# iCEBlaster.net
KiCad netlist of a schematic drawn in EAGLE
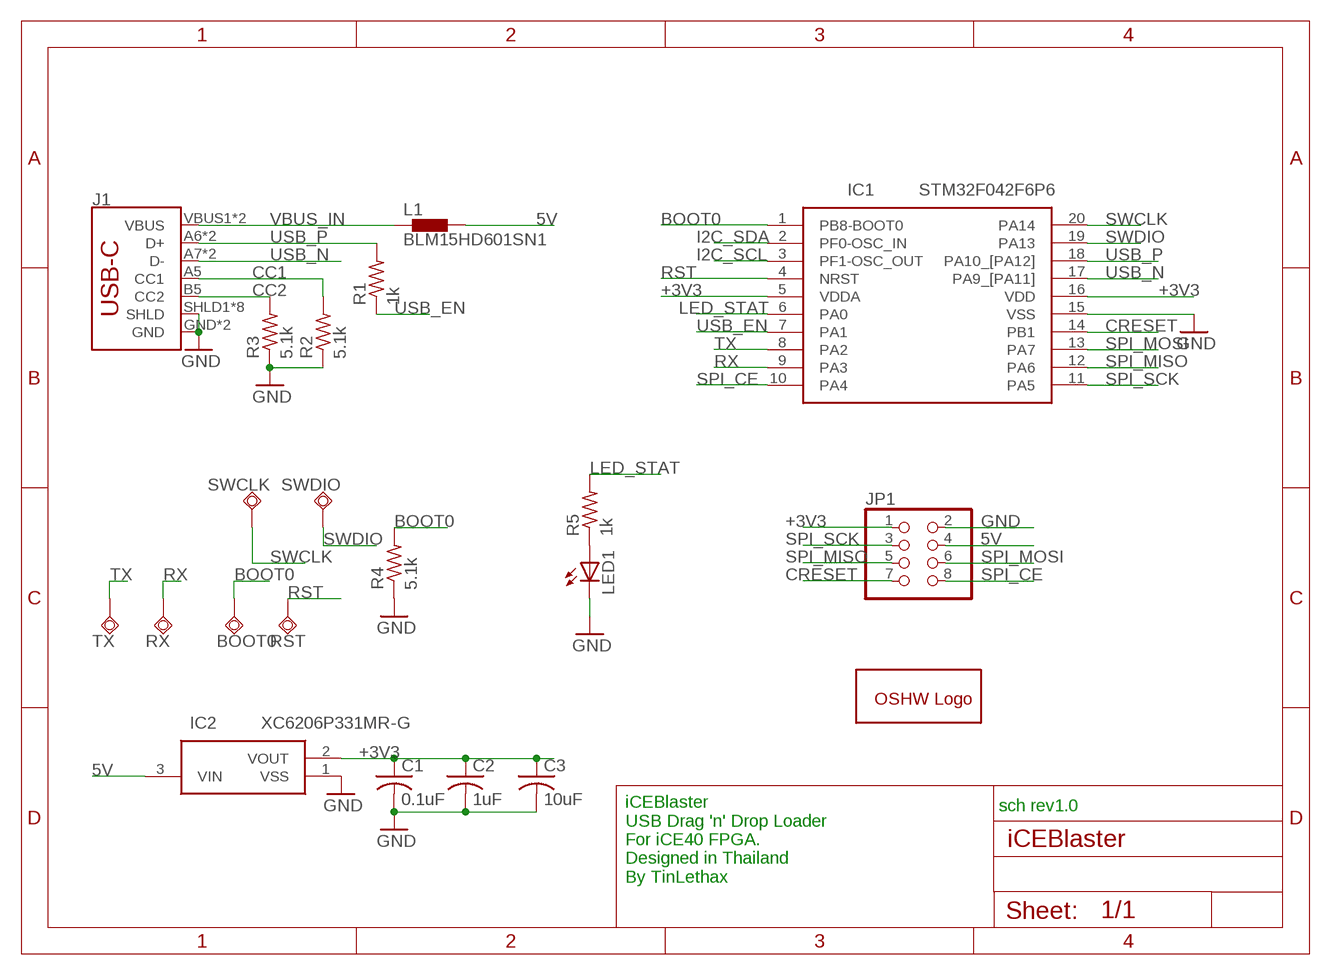
[diagram p0: schematic, sheet 1]

(export (version "E")
  (design (tool "Eeschema 10.0.6"))
  (components
    (comp (ref "BOOT0")
      (value "TPSQTP15SQ")
      (footprint "eagle-import:TP15SQ")
      (libsource (lib "eagle-import") (part "TPSQTP15SQ"))
    )
    (comp (ref "C1")
      (value "0.1uF")
      (footprint "eagle-import:C0603")
      (libsource (lib "eagle-import") (part "C-USC0603"))
    )
    (comp (ref "C2")
      (value "1uF")
      (footprint "eagle-import:C0603")
      (libsource (lib "eagle-import") (part "C-USC0603"))
    )
    (comp (ref "C3")
      (value "10uF")
      (footprint "eagle-import:C0603")
      (libsource (lib "eagle-import") (part "C-USC0603"))
    )
    (comp (ref "GOLD_ORB_SM1")
      (value "OSHWLOGOLOGO5MM")
      (footprint "eagle-import:OSHW_5MM")
      (libsource (lib "eagle-import") (part "OSHWLOGOLOGO5MM"))
    )
    (comp (ref "IC1")
      (value "STM32F042F6P6")
      (footprint "eagle-import:SOP65P640X120-20N")
      (fields (field (name "MOUSER_PART_NUMBER") "511-STM32F042F6P6"))
      (libsource (lib "eagle-import") (part "STM32F042F6P6"))
    )
    (comp (ref "IC2")
      (value "XC6206P331MR-G")
      (footprint "eagle-import:SOT95P280X130-3N")
      (fields (field (name "MOUSER_PART_NUMBER") "865-XC6206P331MR-G"))
      (libsource (lib "eagle-import") (part "XC6206P331MR-G"))
    )
    (comp (ref "J1")
      (value "SPARKFUN-CONNECTORS_USB_C16PIN")
      (footprint "eagle-import:SPARKFUN-CONNECTORS_USB-C-16P")
      (libsource (lib "eagle-import") (part "SPARKFUN-CONNECTORS_USB_C16PIN"))
    )
    (comp (ref "JP1")
      (value "PINHD-2X4/90")
      (footprint "eagle-import:2X04_90")
      (libsource (lib "eagle-import") (part "PINHD-2X4/90"))
    )
    (comp (ref "L1")
      (value "BLM15HD601SN1")
      (footprint "eagle-import:0402")
      (libsource (lib "eagle-import") (part "BLM15HD601SN1"))
    )
    (comp (ref "LED1")
      (value "LEDCHIP-LED0603")
      (footprint "eagle-import:CHIP-LED0603")
      (libsource (lib "eagle-import") (part "LEDCHIP-LED0603"))
    )
    (comp (ref "R1")
      (value "1k")
      (footprint "eagle-import:R0603")
      (libsource (lib "eagle-import") (part "R-US_R0603"))
    )
    (comp (ref "R2")
      (value "5.1k")
      (footprint "eagle-import:R0603")
      (libsource (lib "eagle-import") (part "R-US_R0603"))
    )
    (comp (ref "R3")
      (value "5.1k")
      (footprint "eagle-import:R0603")
      (libsource (lib "eagle-import") (part "R-US_R0603"))
    )
    (comp (ref "R4")
      (value "5.1k")
      (footprint "eagle-import:R0603")
      (libsource (lib "eagle-import") (part "R-US_R0603"))
    )
    (comp (ref "R5")
      (value "1k")
      (footprint "eagle-import:R0603")
      (libsource (lib "eagle-import") (part "R-US_R0603"))
    )
    (comp (ref "RST")
      (value "TPSQTP15SQ")
      (footprint "eagle-import:TP15SQ")
      (libsource (lib "eagle-import") (part "TPSQTP15SQ"))
    )
    (comp (ref "RX")
      (value "TPSQTP15SQ")
      (footprint "eagle-import:TP15SQ")
      (libsource (lib "eagle-import") (part "TPSQTP15SQ"))
    )
    (comp (ref "SWCLK")
      (value "TPSQTP15SQ")
      (footprint "eagle-import:TP15SQ")
      (libsource (lib "eagle-import") (part "TPSQTP15SQ"))
    )
    (comp (ref "SWDIO")
      (value "TPSQTP15SQ")
      (footprint "eagle-import:TP15SQ")
      (libsource (lib "eagle-import") (part "TPSQTP15SQ"))
    )
    (comp (ref "TX")
      (value "TPSQTP15SQ")
      (footprint "eagle-import:TP15SQ")
      (libsource (lib "eagle-import") (part "TPSQTP15SQ"))
    )
  )
  (nets
    (net (code "1") (name "/+3V3") (class "Default")
      (node (ref "C1") (pin "1") (pinfunction "1_1") (pintype "passive"))
      (node (ref "C2") (pin "1") (pinfunction "1_1") (pintype "passive"))
      (node (ref "C3") (pin "1") (pinfunction "1_1") (pintype "passive"))
      (node (ref "IC1") (pin "16") (pinfunction "VDD_16") (pintype "bidirectional"))
      (node (ref "IC1") (pin "5") (pinfunction "VDDA_5") (pintype "bidirectional"))
      (node (ref "IC2") (pin "2") (pinfunction "VOUT_2") (pintype "output"))
      (node (ref "JP1") (pin "1") (pinfunction "1_1") (pintype "passive"))
    )
    (net (code "2") (name "/5V") (class "Default")
      (node (ref "IC2") (pin "3") (pinfunction "VIN_3") (pintype "bidirectional"))
      (node (ref "JP1") (pin "4") (pinfunction "4_4") (pintype "passive"))
      (node (ref "L1") (pin "2") (pinfunction "2_2") (pintype "passive"))
    )
    (net (code "3") (name "/BOOT0") (class "Default")
      (node (ref "BOOT0") (pin "TP") (pinfunction "TP_TP") (pintype "input"))
      (node (ref "IC1") (pin "1") (pinfunction "PB8-BOOT0_1") (pintype "bidirectional"))
      (node (ref "R4") (pin "2") (pinfunction "2_2") (pintype "passive"))
    )
    (net (code "4") (name "/CC1") (class "Default")
      (node (ref "J1") (pin "A5") (pinfunction "CC1_A5") (pintype "bidirectional"))
      (node (ref "R2") (pin "2") (pinfunction "2_2") (pintype "passive"))
    )
    (net (code "5") (name "/CC2") (class "Default")
      (node (ref "J1") (pin "B5") (pinfunction "CC2_B5") (pintype "bidirectional"))
      (node (ref "R3") (pin "2") (pinfunction "2_2") (pintype "passive"))
    )
    (net (code "6") (name "/CRESET") (class "Default")
      (node (ref "IC1") (pin "14") (pinfunction "PB1_14") (pintype "bidirectional"))
      (node (ref "JP1") (pin "7") (pinfunction "7_7") (pintype "passive"))
    )
    (net (code "7") (name "/I2C_SCL") (class "Default")
      (node (ref "IC1") (pin "3") (pinfunction "PF1-OSC_OUT_3") (pintype "bidirectional"))
    )
    (net (code "8") (name "/I2C_SDA") (class "Default")
      (node (ref "IC1") (pin "2") (pinfunction "PF0-OSC_IN_2") (pintype "bidirectional"))
    )
    (net (code "9") (name "/LED_STAT") (class "Default")
      (node (ref "IC1") (pin "6") (pinfunction "PA0_6") (pintype "bidirectional"))
      (node (ref "R5") (pin "2") (pinfunction "2_2") (pintype "passive"))
    )
    (net (code "10") (name "/RST") (class "Default")
      (node (ref "IC1") (pin "4") (pinfunction "NRST_4") (pintype "bidirectional"))
      (node (ref "RST") (pin "TP") (pinfunction "TP_TP") (pintype "input"))
    )
    (net (code "11") (name "/RX") (class "Default")
      (node (ref "IC1") (pin "9") (pinfunction "PA3_9") (pintype "bidirectional"))
      (node (ref "RX") (pin "TP") (pinfunction "TP_TP") (pintype "input"))
    )
    (net (code "12") (name "/SPI_CE") (class "Default")
      (node (ref "IC1") (pin "10") (pinfunction "PA4_10") (pintype "bidirectional"))
      (node (ref "JP1") (pin "8") (pinfunction "8_8") (pintype "passive"))
    )
    (net (code "13") (name "/SPI_MISO") (class "Default")
      (node (ref "IC1") (pin "12") (pinfunction "PA6_12") (pintype "bidirectional"))
      (node (ref "JP1") (pin "5") (pinfunction "5_5") (pintype "passive"))
    )
    (net (code "14") (name "/SPI_MOSI") (class "Default")
      (node (ref "IC1") (pin "13") (pinfunction "PA7_13") (pintype "bidirectional"))
      (node (ref "JP1") (pin "6") (pinfunction "6_6") (pintype "passive"))
    )
    (net (code "15") (name "/SPI_SCK") (class "Default")
      (node (ref "IC1") (pin "11") (pinfunction "PA5_11") (pintype "bidirectional"))
      (node (ref "JP1") (pin "3") (pinfunction "3_3") (pintype "passive"))
    )
    (net (code "16") (name "/SWCLK") (class "Default")
      (node (ref "IC1") (pin "20") (pinfunction "PA14_20") (pintype "bidirectional"))
      (node (ref "SWCLK") (pin "TP") (pinfunction "TP_TP") (pintype "input"))
    )
    (net (code "17") (name "/SWDIO") (class "Default")
      (node (ref "IC1") (pin "19") (pinfunction "PA13_19") (pintype "bidirectional"))
      (node (ref "SWDIO") (pin "TP") (pinfunction "TP_TP") (pintype "input"))
    )
    (net (code "18") (name "/TX") (class "Default")
      (node (ref "IC1") (pin "8") (pinfunction "PA2_8") (pintype "bidirectional"))
      (node (ref "TX") (pin "TP") (pinfunction "TP_TP") (pintype "input"))
    )
    (net (code "19") (name "/USB_EN") (class "Default")
      (node (ref "IC1") (pin "7") (pinfunction "PA1_7") (pintype "bidirectional"))
      (node (ref "R1") (pin "1") (pinfunction "1_1") (pintype "passive"))
    )
    (net (code "20") (name "/USB_N") (class "Default")
      (node (ref "IC1") (pin "17") (pinfunction "PA9_[PA11]_17") (pintype "bidirectional"))
      (node (ref "J1") (pin "A7") (pinfunction "D-_A7") (pintype "bidirectional"))
      (node (ref "J1") (pin "B7") (pinfunction "D-_B7") (pintype "bidirectional"))
    )
    (net (code "21") (name "/USB_P") (class "Default")
      (node (ref "IC1") (pin "18") (pinfunction "PA10_[PA12]_18") (pintype "bidirectional"))
      (node (ref "J1") (pin "A6") (pinfunction "D+_A6") (pintype "bidirectional"))
      (node (ref "J1") (pin "B6") (pinfunction "D+_B6") (pintype "bidirectional"))
      (node (ref "R1") (pin "2") (pinfunction "2_2") (pintype "passive"))
    )
    (net (code "22") (name "/VBUS_IN") (class "Default")
      (node (ref "J1") (pin "VBUS1") (pinfunction "VBUS_VBUS1") (pintype "bidirectional"))
      (node (ref "J1") (pin "VBUS2") (pinfunction "VBUS_VBUS2") (pintype "bidirectional"))
      (node (ref "L1") (pin "1") (pinfunction "1_1") (pintype "passive"))
    )
    (net (code "23") (name "GND") (class "Default")
      (node (ref "C1") (pin "2") (pinfunction "2_2") (pintype "passive"))
      (node (ref "C2") (pin "2") (pinfunction "2_2") (pintype "passive"))
      (node (ref "C3") (pin "2") (pinfunction "2_2") (pintype "passive"))
      (node (ref "IC1") (pin "15") (pinfunction "VSS_15") (pintype "bidirectional"))
      (node (ref "IC2") (pin "1") (pinfunction "VSS_1") (pintype "power_in"))
      (node (ref "J1") (pin "GND") (pinfunction "GND_GND") (pintype "bidirectional"))
      (node (ref "J1") (pin "GND2") (pinfunction "GND_GND2") (pintype "bidirectional"))
      (node (ref "J1") (pin "SHLD1") (pinfunction "SHLD_SHLD1") (pintype "bidirectional"))
      (node (ref "J1") (pin "SHLD2") (pinfunction "SHLD_SHLD2") (pintype "bidirectional"))
      (node (ref "J1") (pin "SHLD3") (pinfunction "SHLD_SHLD3") (pintype "bidirectional"))
      (node (ref "J1") (pin "SHLD4") (pinfunction "SHLD_SHLD4") (pintype "bidirectional"))
      (node (ref "J1") (pin "SHLD5") (pinfunction "SHLD_SHLD5") (pintype "bidirectional"))
      (node (ref "J1") (pin "SHLD6") (pinfunction "SHLD_SHLD6") (pintype "bidirectional"))
      (node (ref "J1") (pin "SHLD7") (pinfunction "SHLD_SHLD7") (pintype "bidirectional"))
      (node (ref "J1") (pin "SHLD8") (pinfunction "SHLD_SHLD8") (pintype "bidirectional"))
      (node (ref "JP1") (pin "2") (pinfunction "2_2") (pintype "passive"))
      (node (ref "LED1") (pin "C") (pinfunction "C_C") (pintype "passive"))
      (node (ref "R2") (pin "1") (pinfunction "1_1") (pintype "passive"))
      (node (ref "R3") (pin "1") (pinfunction "1_1") (pintype "passive"))
      (node (ref "R4") (pin "1") (pinfunction "1_1") (pintype "passive"))
    )
    (net (code "24") (name "Net-(LED1-PadA)") (class "Default")
      (node (ref "LED1") (pin "A") (pinfunction "A_A") (pintype "passive"))
      (node (ref "R5") (pin "1") (pinfunction "1_1") (pintype "passive"))
    )
  )
)
